# TestBoardV1.net
KiCad netlist of a schematic drawn in Altium Designer
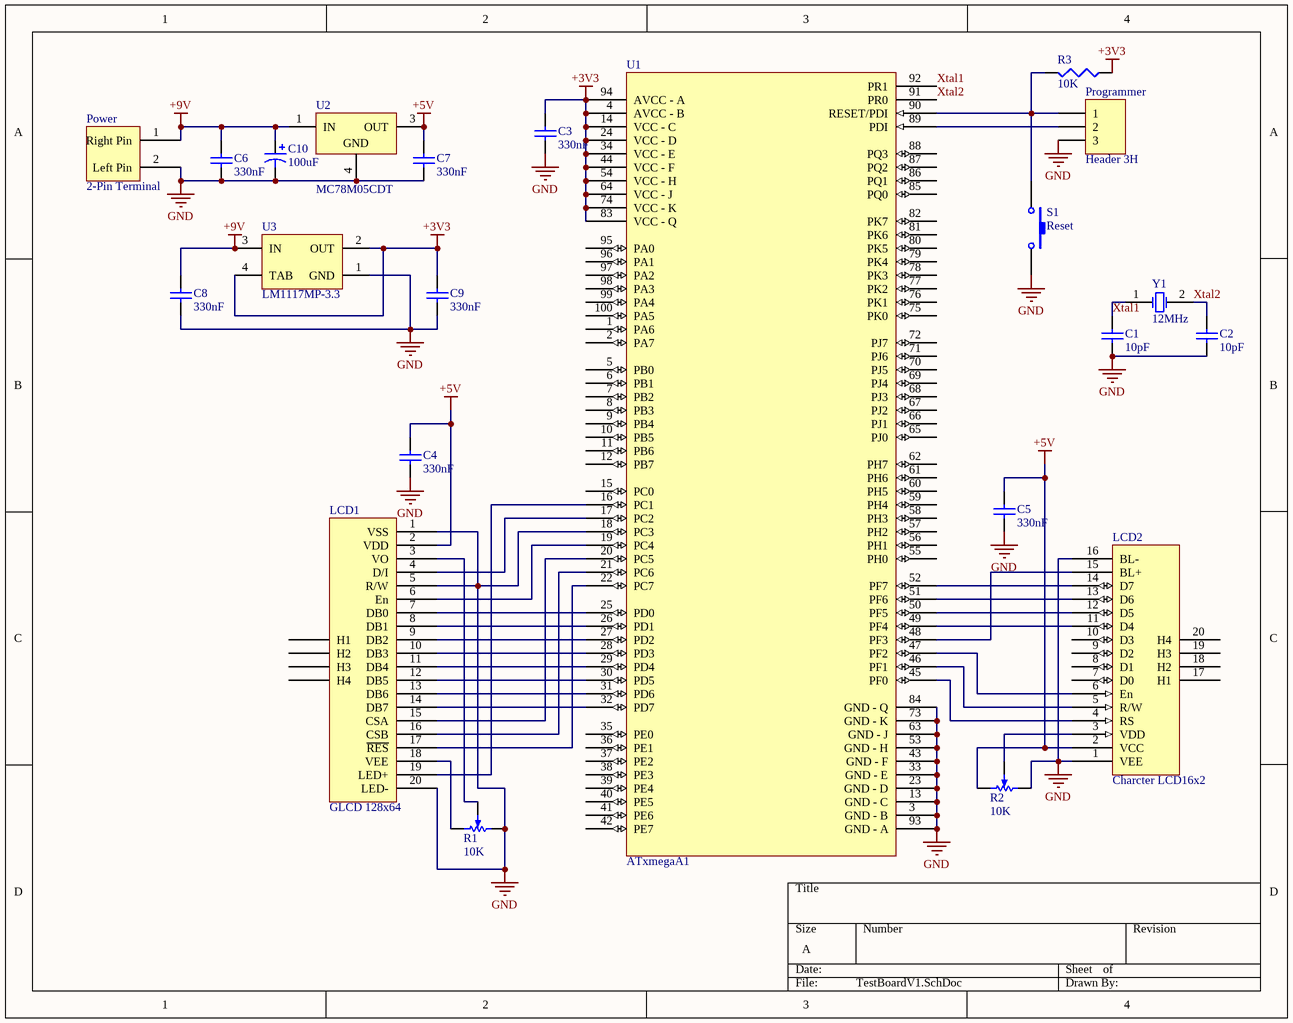
[diagram p0: TestBoardV1.SchDoc]

(export (version "E")
  (design (tool "Eeschema 10.0.6"))
  (components
    (comp (ref "C1")
      (value "10pF")
      (footprint "C1206")
      (description "Capacitor (Semiconductor SIM Model)")
      (fields (field (name "Comment") "Cap Semi") (field (name "PUBLISHER") "Altium Limited"))
      (libsource (lib "Miscellaneous Devices") (part "Cap Semi"))
    )
    (comp (ref "C2")
      (value "10pF")
      (footprint "C1206")
      (description "Capacitor (Semiconductor SIM Model)")
      (fields (field (name "Comment") "Cap Semi") (field (name "PUBLISHER") "Altium Limited"))
      (libsource (lib "Miscellaneous Devices") (part "Cap Semi"))
    )
    (comp (ref "C3")
      (value "330nF")
      (footprint "C1206")
      (description "Capacitor (Semiconductor SIM Model)")
      (fields (field (name "Comment") "Cap Semi") (field (name "PUBLISHER") "Altium Limited"))
      (libsource (lib "Miscellaneous Devices") (part "Cap Semi"))
    )
    (comp (ref "C4")
      (value "330nF")
      (footprint "C1206")
      (description "Capacitor (Semiconductor SIM Model)")
      (fields (field (name "Comment") "Cap Semi") (field (name "PUBLISHER") "Altium Limited"))
      (libsource (lib "Miscellaneous Devices") (part "Cap Semi"))
    )
    (comp (ref "C5")
      (value "330nF")
      (footprint "C1206")
      (description "Capacitor (Semiconductor SIM Model)")
      (fields (field (name "Comment") "Cap Semi") (field (name "PUBLISHER") "Altium Limited"))
      (libsource (lib "Miscellaneous Devices") (part "Cap Semi"))
    )
    (comp (ref "C6")
      (value "330nF")
      (footprint "C1206")
      (description "Capacitor (Semiconductor SIM Model)")
      (fields (field (name "Comment") "Cap Semi") (field (name "PUBLISHER") "Altium Limited"))
      (libsource (lib "Miscellaneous Devices") (part "Cap Semi"))
    )
    (comp (ref "C7")
      (value "330nF")
      (footprint "C1206")
      (description "Capacitor (Semiconductor SIM Model)")
      (fields (field (name "Comment") "Cap Semi") (field (name "PUBLISHER") "Altium Limited"))
      (libsource (lib "Miscellaneous Devices") (part "Cap Semi"))
    )
    (comp (ref "C8")
      (value "330nF")
      (footprint "C1206")
      (description "Capacitor (Semiconductor SIM Model)")
      (fields (field (name "Comment") "Cap Semi") (field (name "PUBLISHER") "Altium Limited"))
      (libsource (lib "Miscellaneous Devices") (part "Cap Semi"))
    )
    (comp (ref "C9")
      (value "330nF")
      (footprint "C1206")
      (description "Capacitor (Semiconductor SIM Model)")
      (fields (field (name "Comment") "Cap Semi") (field (name "PUBLISHER") "Altium Limited"))
      (libsource (lib "Miscellaneous Devices") (part "Cap Semi"))
    )
    (comp (ref "C10") (value "100uF") (footprint "Cap Pole-100u") (libsource (lib "MyLib") (part "Cap Pole")))
    (comp (ref "LCD1")
      (value "GLCD 128x64")
      (footprint "GLCD 128X64")
      (libsource (lib "MyLib") (part "GLCD 128x64"))
    )
    (comp (ref "LCD2")
      (value "Charcter LCD16x2")
      (footprint "LCD16x2")
      (libsource (lib "MyLib") (part "LCD16x2"))
    )
    (comp (ref "Power")
      (value "2-Pin Terminal")
      (footprint "2-pin Terminal")
      (libsource (lib "MyLib") (part "2-Pin Terminal"))
    )
    (comp (ref "Programmer")
      (value "Header 3H")
      (footprint "HDR1X3H")
      (description "Header, 3-Pin, Right Angle")
      (fields (field (name "PUBLISHER") "Altium Limited"))
      (libsource (lib "Miscellaneous Connectors") (part "Header 3H"))
    )
    (comp (ref "R1")
      (value "10K")
      (footprint "POT4MM-2")
      (description "Square Trimming Potentiometer")
      (fields (field (name "PUBLISHER") "Altium Limited"))
      (libsource (lib "Miscellaneous Devices") (part "RPot SM"))
    )
    (comp (ref "R2")
      (value "10K")
      (footprint "POT4MM-2")
      (description "Square Trimming Potentiometer")
      (fields (field (name "PUBLISHER") "Altium Limited"))
      (libsource (lib "Miscellaneous Devices") (part "RPot SM"))
    )
    (comp (ref "R3")
      (value "10K")
      (footprint "MELF-R3216-1206")
      (description "Resistor")
      (fields (field (name "Comment") "Res3") (field (name "PUBLISHER") "Altium Limited"))
      (libsource (lib "Miscellaneous Devices") (part "Res3"))
    )
    (comp (ref "S1")
      (value "Reset")
      (footprint "SMD_Switch")
      (description "Switch")
      (fields (field (name "PUBLISHER") "Altium Limited"))
      (libsource (lib "Miscellaneous Devices") (part "SW-PB"))
    )
    (comp (ref "U1")
      (value "ATxmegaA1")
      (footprint "TQFP100")
      (description "High Performance 8/16bit MCU")
      (libsource (lib "MyLib") (part "ATxMega_A1"))
    )
    (comp (ref "U2")
      (value "MC78M05CDT")
      (footprint "369A-03")
      (description "3-Terminal Medium-Current Positive Fixed Voltage Regulator")
      (fields (field (name "PUBLISHER") "Altium Limited"))
      (libsource (lib "Motorola Power Mgt Voltage Regulator") (part "MC78M05CDT"))
    )
    (comp (ref "U3")
      (value "LM1117MP-3.3")
      (footprint "MP04A_N")
      (description "800mA Low-Dropout Linear Regulator")
      (fields
        (field (name "MANUFACTURER") "National Semiconductor")
        (field (name "DIGIKEYPARTNUMBER") "LM1117MP-3.3CT-ND")
        (field (name "PUBLISHER") "Altium Limited")
      )
      (libsource (lib "NSC LDO") (part "LM1117MP-3.3"))
    )
    (comp (ref "Y1")
      (value "12MHz")
      (footprint "HC-49U")
      (description "Crystal Oscillator")
      (fields (field (name "PUBLISHER") "Altium Limited"))
      (libsource (lib "ECS Crystal Oscillator") (part "ECS-10-13-1"))
    )
  )
  (nets
    (net (code "1") (name "+3V3") (class "Default")
      (node (ref "C3") (pin "2") (pinfunction "2_2") (pintype "passive"))
      (node (ref "C9") (pin "2") (pinfunction "2_2") (pintype "passive"))
      (node (ref "R3") (pin "1") (pinfunction "1_1") (pintype "passive"))
      (node (ref "U1") (pin "14") (pinfunction "VCC_-_C_14") (pintype "power_in"))
      (node (ref "U1") (pin "24") (pinfunction "VCC_-_D_24") (pintype "power_in"))
      (node (ref "U1") (pin "34") (pinfunction "VCC_-_E_34") (pintype "power_in"))
      (node (ref "U1") (pin "4") (pinfunction "AVCC_-_B_4") (pintype "power_in"))
      (node (ref "U1") (pin "44") (pinfunction "VCC_-_F_44") (pintype "power_in"))
      (node (ref "U1") (pin "54") (pinfunction "VCC_-_H_54") (pintype "power_in"))
      (node (ref "U1") (pin "64") (pinfunction "VCC_-_J_64") (pintype "power_in"))
      (node (ref "U1") (pin "74") (pinfunction "VCC_-_K_74") (pintype "power_in"))
      (node (ref "U1") (pin "83") (pinfunction "VCC_-_Q_83") (pintype "power_in"))
      (node (ref "U1") (pin "94") (pinfunction "AVCC_-_A_94") (pintype "power_in"))
      (node (ref "U3") (pin "2") (pinfunction "OUT_2") (pintype "power_in"))
      (node (ref "U3") (pin "4") (pinfunction "TAB_4") (pintype "power_in"))
    )
    (net (code "2") (name "+5V") (class "Default")
      (node (ref "C4") (pin "2") (pinfunction "2_2") (pintype "passive"))
      (node (ref "C5") (pin "2") (pinfunction "2_2") (pintype "passive"))
      (node (ref "C7") (pin "2") (pinfunction "2_2") (pintype "passive"))
      (node (ref "LCD1") (pin "2") (pinfunction "VDD_2") (pintype "passive"))
      (node (ref "LCD2") (pin "2") (pinfunction "VCC_2") (pintype "power_in"))
      (node (ref "R2") (pin "CW") (pinfunction "+_CW") (pintype "passive"))
      (node (ref "U2") (pin "3") (pinfunction "OUT_3") (pintype "power_in"))
    )
    (net (code "3") (name "+9V") (class "Default")
      (node (ref "C10") (pin "1") (pinfunction "1_1") (pintype "passive"))
      (node (ref "C6") (pin "2") (pinfunction "2_2") (pintype "passive"))
      (node (ref "C8") (pin "2") (pinfunction "2_2") (pintype "passive"))
      (node (ref "Power") (pin "1") (pinfunction "Right_Pin_1") (pintype "power_in"))
      (node (ref "U2") (pin "1") (pinfunction "IN_1") (pintype "power_in"))
      (node (ref "U3") (pin "3") (pinfunction "IN_3") (pintype "power_in"))
    )
    (net (code "4") (name "/Xtal1") (class "Default")
      (node (ref "C1") (pin "1") (pinfunction "1_1") (pintype "passive"))
      (node (ref "U1") (pin "92") (pinfunction "PR1_92") (pintype "power_in"))
      (node (ref "Y1") (pin "1") (pinfunction "OSC1_1") (pintype "passive"))
    )
    (net (code "5") (name "/Xtal2") (class "Default")
      (node (ref "C2") (pin "2") (pinfunction "2_2") (pintype "passive"))
      (node (ref "U1") (pin "91") (pinfunction "PR0_91") (pintype "power_in"))
      (node (ref "Y1") (pin "2") (pinfunction "OSC2_2") (pintype "passive"))
    )
    (net (code "6") (name "GND") (class "Default")
      (node (ref "C1") (pin "2") (pinfunction "2_2") (pintype "passive"))
      (node (ref "C10") (pin "2") (pinfunction "2_2") (pintype "passive"))
      (node (ref "C2") (pin "1") (pinfunction "1_1") (pintype "passive"))
      (node (ref "C3") (pin "1") (pinfunction "1_1") (pintype "passive"))
      (node (ref "C4") (pin "1") (pinfunction "1_1") (pintype "passive"))
      (node (ref "C5") (pin "1") (pinfunction "1_1") (pintype "passive"))
      (node (ref "C6") (pin "1") (pinfunction "1_1") (pintype "passive"))
      (node (ref "C7") (pin "1") (pinfunction "1_1") (pintype "passive"))
      (node (ref "C8") (pin "1") (pinfunction "1_1") (pintype "passive"))
      (node (ref "C9") (pin "1") (pinfunction "1_1") (pintype "passive"))
      (node (ref "LCD1") (pin "1") (pinfunction "VSS_1") (pintype "passive"))
      (node (ref "LCD1") (pin "20") (pinfunction "LED-_20") (pintype "passive"))
      (node (ref "LCD1") (pin "5") (pinfunction "R/W_5") (pintype "passive"))
      (node (ref "LCD2") (pin "1") (pinfunction "VEE_1") (pintype "power_in"))
      (node (ref "LCD2") (pin "16") (pinfunction "BL-_16") (pintype "passive"))
      (node (ref "Power") (pin "2") (pinfunction "Left_Pin_2") (pintype "power_in"))
      (node (ref "Programmer") (pin "3") (pinfunction "3_3") (pintype "passive"))
      (node (ref "R1") (pin "CCW") (pinfunction "-_CCW") (pintype "passive"))
      (node (ref "R2") (pin "CCW") (pinfunction "-_CCW") (pintype "passive"))
      (node (ref "S1") (pin "1") (pinfunction "1_1") (pintype "passive"))
      (node (ref "U1") (pin "13") (pinfunction "GND_-_C_13") (pintype "power_in"))
      (node (ref "U1") (pin "18") (pinfunction "PC3_18") (pintype "bidirectional"))
      (node (ref "U1") (pin "23") (pinfunction "GND_-_D_23") (pintype "power_in"))
      (node (ref "U1") (pin "3") (pinfunction "GND_-_B_3") (pintype "power_in"))
      (node (ref "U1") (pin "33") (pinfunction "GND_-_E_33") (pintype "power_in"))
      (node (ref "U1") (pin "43") (pinfunction "GND_-_F_43") (pintype "power_in"))
      (node (ref "U1") (pin "53") (pinfunction "GND_-_H_53") (pintype "power_in"))
      (node (ref "U1") (pin "63") (pinfunction "GND_-_J_63") (pintype "power_in"))
      (node (ref "U1") (pin "73") (pinfunction "GND_-_K_73") (pintype "power_in"))
      (node (ref "U1") (pin "84") (pinfunction "GND_-_Q_84") (pintype "power_in"))
      (node (ref "U1") (pin "93") (pinfunction "GND_-_A_93") (pintype "power_in"))
      (node (ref "U2") (pin "4") (pinfunction "GND_4") (pintype "power_in"))
      (node (ref "U3") (pin "1") (pinfunction "GND_1") (pintype "power_in"))
    )
    (net (code "7") (name "Net-(LCD1-CSA)") (class "Default")
      (node (ref "LCD1") (pin "15") (pinfunction "CSA_15") (pintype "passive"))
      (node (ref "U1") (pin "20") (pinfunction "PC5_20") (pintype "bidirectional"))
    )
    (net (code "8") (name "Net-(LCD1-CSB)") (class "Default")
      (node (ref "LCD1") (pin "16") (pinfunction "CSB_16") (pintype "passive"))
      (node (ref "U1") (pin "21") (pinfunction "PC6_21") (pintype "bidirectional"))
    )
    (net (code "9") (name "Net-(LCD1-DB0)") (class "Default")
      (node (ref "LCD1") (pin "7") (pinfunction "DB0_7") (pintype "passive"))
      (node (ref "U1") (pin "25") (pinfunction "PD0_25") (pintype "bidirectional"))
    )
    (net (code "10") (name "Net-(LCD1-DB1)") (class "Default")
      (node (ref "LCD1") (pin "8") (pinfunction "DB1_8") (pintype "passive"))
      (node (ref "U1") (pin "26") (pinfunction "PD1_26") (pintype "bidirectional"))
    )
    (net (code "11") (name "Net-(LCD1-DB2)") (class "Default")
      (node (ref "LCD1") (pin "9") (pinfunction "DB2_9") (pintype "passive"))
      (node (ref "U1") (pin "27") (pinfunction "PD2_27") (pintype "bidirectional"))
    )
    (net (code "12") (name "Net-(LCD1-DB3)") (class "Default")
      (node (ref "LCD1") (pin "10") (pinfunction "DB3_10") (pintype "passive"))
      (node (ref "U1") (pin "28") (pinfunction "PD3_28") (pintype "bidirectional"))
    )
    (net (code "13") (name "Net-(LCD1-DB4)") (class "Default")
      (node (ref "LCD1") (pin "11") (pinfunction "DB4_11") (pintype "passive"))
      (node (ref "U1") (pin "29") (pinfunction "PD4_29") (pintype "bidirectional"))
    )
    (net (code "14") (name "Net-(LCD1-DB5)") (class "Default")
      (node (ref "LCD1") (pin "12") (pinfunction "DB5_12") (pintype "passive"))
      (node (ref "U1") (pin "30") (pinfunction "PD5_30") (pintype "bidirectional"))
    )
    (net (code "15") (name "Net-(LCD1-DB6)") (class "Default")
      (node (ref "LCD1") (pin "13") (pinfunction "DB6_13") (pintype "passive"))
      (node (ref "U1") (pin "31") (pinfunction "PD6_31") (pintype "bidirectional"))
    )
    (net (code "16") (name "Net-(LCD1-DB7)") (class "Default")
      (node (ref "LCD1") (pin "14") (pinfunction "DB7_14") (pintype "passive"))
      (node (ref "U1") (pin "32") (pinfunction "PD7_32") (pintype "bidirectional"))
    )
    (net (code "17") (name "Net-(LCD1-D{slash}I)") (class "Default")
      (node (ref "LCD1") (pin "4") (pinfunction "D/I_4") (pintype "passive"))
      (node (ref "U1") (pin "17") (pinfunction "PC2_17") (pintype "bidirectional"))
    )
    (net (code "18") (name "Net-(LCD1-En)") (class "Default")
      (node (ref "LCD1") (pin "6") (pinfunction "En_6") (pintype "passive"))
      (node (ref "U1") (pin "19") (pinfunction "PC4_19") (pintype "bidirectional"))
    )
    (net (code "19") (name "Net-(LCD1-LED+)") (class "Default")
      (node (ref "LCD1") (pin "19") (pinfunction "LED+_19") (pintype "passive"))
      (node (ref "U1") (pin "16") (pinfunction "PC1_16") (pintype "bidirectional"))
    )
    (net (code "20") (name "Net-(LCD1-VEE)") (class "Default")
      (node (ref "LCD1") (pin "18") (pinfunction "VEE_18") (pintype "passive"))
      (node (ref "R1") (pin "CW") (pinfunction "+_CW") (pintype "passive"))
    )
    (net (code "21") (name "Net-(LCD1-VO)") (class "Default")
      (node (ref "LCD1") (pin "3") (pinfunction "VO_3") (pintype "passive"))
      (node (ref "R1") (pin "W") (pinfunction "W_W") (pintype "passive"))
    )
    (net (code "22") (name "Net-(LCD1-~{RES})") (class "Default")
      (node (ref "LCD1") (pin "17") (pinfunction "~{RES}_17") (pintype "passive"))
      (node (ref "U1") (pin "22") (pinfunction "PC7_22") (pintype "bidirectional"))
    )
    (net (code "23") (name "Net-(LCD2-BL+)") (class "Default")
      (node (ref "LCD2") (pin "15") (pinfunction "BL+_15") (pintype "passive"))
      (node (ref "U1") (pin "48") (pinfunction "PF3_48") (pintype "bidirectional"))
    )
    (net (code "24") (name "Net-(LCD2-D4)") (class "Default")
      (node (ref "LCD2") (pin "11") (pinfunction "D4_11") (pintype "bidirectional"))
      (node (ref "U1") (pin "49") (pinfunction "PF4_49") (pintype "bidirectional"))
    )
    (net (code "25") (name "Net-(LCD2-D5)") (class "Default")
      (node (ref "LCD2") (pin "12") (pinfunction "D5_12") (pintype "bidirectional"))
      (node (ref "U1") (pin "50") (pinfunction "PF5_50") (pintype "bidirectional"))
    )
    (net (code "26") (name "Net-(LCD2-D6)") (class "Default")
      (node (ref "LCD2") (pin "13") (pinfunction "D6_13") (pintype "bidirectional"))
      (node (ref "U1") (pin "51") (pinfunction "PF6_51") (pintype "bidirectional"))
    )
    (net (code "27") (name "Net-(LCD2-D7)") (class "Default")
      (node (ref "LCD2") (pin "14") (pinfunction "D7_14") (pintype "bidirectional"))
      (node (ref "U1") (pin "52") (pinfunction "PF7_52") (pintype "bidirectional"))
    )
    (net (code "28") (name "Net-(LCD2-En)") (class "Default")
      (node (ref "LCD2") (pin "6") (pinfunction "En_6") (pintype "input"))
      (node (ref "U1") (pin "47") (pinfunction "PF2_47") (pintype "bidirectional"))
    )
    (net (code "29") (name "Net-(LCD2-RS)") (class "Default")
      (node (ref "LCD2") (pin "4") (pinfunction "RS_4") (pintype "input"))
      (node (ref "U1") (pin "45") (pinfunction "PF0_45") (pintype "bidirectional"))
    )
    (net (code "30") (name "Net-(LCD2-R{slash}W)") (class "Default")
      (node (ref "LCD2") (pin "5") (pinfunction "R/W_5") (pintype "input"))
      (node (ref "U1") (pin "46") (pinfunction "PF1_46") (pintype "bidirectional"))
    )
    (net (code "31") (name "Net-(LCD2-VDD)") (class "Default")
      (node (ref "LCD2") (pin "3") (pinfunction "VDD_3") (pintype "input"))
      (node (ref "R2") (pin "W") (pinfunction "W_W") (pintype "passive"))
    )
    (net (code "32") (name "Net-(U1-PDI)") (class "Default")
      (node (ref "Programmer") (pin "2") (pinfunction "2_2") (pintype "passive"))
      (node (ref "U1") (pin "89") (pinfunction "PDI_89") (pintype "input"))
    )
    (net (code "33") (name "Net-(U1-RESET{slash}PDI)") (class "Default")
      (node (ref "Programmer") (pin "1") (pinfunction "1_1") (pintype "passive"))
      (node (ref "R3") (pin "2") (pinfunction "2_2") (pintype "passive"))
      (node (ref "S1") (pin "2") (pinfunction "2_2") (pintype "passive"))
      (node (ref "U1") (pin "90") (pinfunction "RESET/PDI_90") (pintype "input"))
    )
    (net (code "34") (name "unconnected-(LCD1-H1-Pad21)") (class "Default")
      (node (ref "LCD1") (pin "21") (pinfunction "H1_21") (pintype "passive"))
    )
    (net (code "35") (name "unconnected-(LCD1-H2-Pad22)") (class "Default")
      (node (ref "LCD1") (pin "22") (pinfunction "H2_22") (pintype "passive"))
    )
    (net (code "36") (name "unconnected-(LCD1-H3-Pad23)") (class "Default")
      (node (ref "LCD1") (pin "23") (pinfunction "H3_23") (pintype "passive"))
    )
    (net (code "37") (name "unconnected-(LCD1-H4-Pad24)") (class "Default")
      (node (ref "LCD1") (pin "24") (pinfunction "H4_24") (pintype "passive"))
    )
    (net (code "38") (name "unconnected-(LCD2-D0-Pad7)") (class "Default")
      (node (ref "LCD2") (pin "7") (pinfunction "D0_7") (pintype "bidirectional"))
    )
    (net (code "39") (name "unconnected-(LCD2-D1-Pad8)") (class "Default")
      (node (ref "LCD2") (pin "8") (pinfunction "D1_8") (pintype "bidirectional"))
    )
    (net (code "40") (name "unconnected-(LCD2-D2-Pad9)") (class "Default")
      (node (ref "LCD2") (pin "9") (pinfunction "D2_9") (pintype "bidirectional"))
    )
    (net (code "41") (name "unconnected-(LCD2-D3-Pad10)") (class "Default")
      (node (ref "LCD2") (pin "10") (pinfunction "D3_10") (pintype "bidirectional"))
    )
    (net (code "42") (name "unconnected-(LCD2-H1-Pad17)") (class "Default")
      (node (ref "LCD2") (pin "17") (pinfunction "H1_17") (pintype "passive"))
    )
    (net (code "43") (name "unconnected-(LCD2-H2-Pad18)") (class "Default")
      (node (ref "LCD2") (pin "18") (pinfunction "H2_18") (pintype "passive"))
    )
    (net (code "44") (name "unconnected-(LCD2-H3-Pad19)") (class "Default")
      (node (ref "LCD2") (pin "19") (pinfunction "H3_19") (pintype "passive"))
    )
    (net (code "45") (name "unconnected-(LCD2-H4-Pad20)") (class "Default")
      (node (ref "LCD2") (pin "20") (pinfunction "H4_20") (pintype "passive"))
    )
    (net (code "46") (name "unconnected-(U1-PA0-Pad95)") (class "Default")
      (node (ref "U1") (pin "95") (pinfunction "PA0_95") (pintype "bidirectional"))
    )
    (net (code "47") (name "unconnected-(U1-PA1-Pad96)") (class "Default")
      (node (ref "U1") (pin "96") (pinfunction "PA1_96") (pintype "bidirectional"))
    )
    (net (code "48") (name "unconnected-(U1-PA2-Pad97)") (class "Default")
      (node (ref "U1") (pin "97") (pinfunction "PA2_97") (pintype "bidirectional"))
    )
    (net (code "49") (name "unconnected-(U1-PA3-Pad98)") (class "Default")
      (node (ref "U1") (pin "98") (pinfunction "PA3_98") (pintype "bidirectional"))
    )
    (net (code "50") (name "unconnected-(U1-PA4-Pad99)") (class "Default")
      (node (ref "U1") (pin "99") (pinfunction "PA4_99") (pintype "bidirectional"))
    )
    (net (code "51") (name "unconnected-(U1-PA5-Pad100)") (class "Default")
      (node (ref "U1") (pin "100") (pinfunction "PA5_100") (pintype "bidirectional"))
    )
    (net (code "52") (name "unconnected-(U1-PA6-Pad1)") (class "Default")
      (node (ref "U1") (pin "1") (pinfunction "PA6_1") (pintype "bidirectional"))
    )
    (net (code "53") (name "unconnected-(U1-PA7-Pad2)") (class "Default")
      (node (ref "U1") (pin "2") (pinfunction "PA7_2") (pintype "bidirectional"))
    )
    (net (code "54") (name "unconnected-(U1-PB0-Pad5)") (class "Default")
      (node (ref "U1") (pin "5") (pinfunction "PB0_5") (pintype "bidirectional"))
    )
    (net (code "55") (name "unconnected-(U1-PB1-Pad6)") (class "Default")
      (node (ref "U1") (pin "6") (pinfunction "PB1_6") (pintype "bidirectional"))
    )
    (net (code "56") (name "unconnected-(U1-PB2-Pad7)") (class "Default")
      (node (ref "U1") (pin "7") (pinfunction "PB2_7") (pintype "bidirectional"))
    )
    (net (code "57") (name "unconnected-(U1-PB3-Pad8)") (class "Default")
      (node (ref "U1") (pin "8") (pinfunction "PB3_8") (pintype "bidirectional"))
    )
    (net (code "58") (name "unconnected-(U1-PB4-Pad9)") (class "Default")
      (node (ref "U1") (pin "9") (pinfunction "PB4_9") (pintype "bidirectional"))
    )
    (net (code "59") (name "unconnected-(U1-PB5-Pad10)") (class "Default")
      (node (ref "U1") (pin "10") (pinfunction "PB5_10") (pintype "bidirectional"))
    )
    (net (code "60") (name "unconnected-(U1-PB6-Pad11)") (class "Default")
      (node (ref "U1") (pin "11") (pinfunction "PB6_11") (pintype "bidirectional"))
    )
    (net (code "61") (name "unconnected-(U1-PB7-Pad12)") (class "Default")
      (node (ref "U1") (pin "12") (pinfunction "PB7_12") (pintype "bidirectional"))
    )
    (net (code "62") (name "unconnected-(U1-PC0-Pad15)") (class "Default")
      (node (ref "U1") (pin "15") (pinfunction "PC0_15") (pintype "bidirectional"))
    )
    (net (code "63") (name "unconnected-(U1-PE0-Pad35)") (class "Default")
      (node (ref "U1") (pin "35") (pinfunction "PE0_35") (pintype "bidirectional"))
    )
    (net (code "64") (name "unconnected-(U1-PE1-Pad36)") (class "Default")
      (node (ref "U1") (pin "36") (pinfunction "PE1_36") (pintype "bidirectional"))
    )
    (net (code "65") (name "unconnected-(U1-PE2-Pad37)") (class "Default")
      (node (ref "U1") (pin "37") (pinfunction "PE2_37") (pintype "bidirectional"))
    )
    (net (code "66") (name "unconnected-(U1-PE3-Pad38)") (class "Default")
      (node (ref "U1") (pin "38") (pinfunction "PE3_38") (pintype "bidirectional"))
    )
    (net (code "67") (name "unconnected-(U1-PE4-Pad39)") (class "Default")
      (node (ref "U1") (pin "39") (pinfunction "PE4_39") (pintype "bidirectional"))
    )
    (net (code "68") (name "unconnected-(U1-PE5-Pad40)") (class "Default")
      (node (ref "U1") (pin "40") (pinfunction "PE5_40") (pintype "bidirectional"))
    )
    (net (code "69") (name "unconnected-(U1-PE6-Pad41)") (class "Default")
      (node (ref "U1") (pin "41") (pinfunction "PE6_41") (pintype "bidirectional"))
    )
    (net (code "70") (name "unconnected-(U1-PE7-Pad42)") (class "Default")
      (node (ref "U1") (pin "42") (pinfunction "PE7_42") (pintype "bidirectional"))
    )
    (net (code "71") (name "unconnected-(U1-PH0-Pad55)") (class "Default")
      (node (ref "U1") (pin "55") (pinfunction "PH0_55") (pintype "bidirectional"))
    )
    (net (code "72") (name "unconnected-(U1-PH1-Pad56)") (class "Default")
      (node (ref "U1") (pin "56") (pinfunction "PH1_56") (pintype "bidirectional"))
    )
    (net (code "73") (name "unconnected-(U1-PH2-Pad57)") (class "Default")
      (node (ref "U1") (pin "57") (pinfunction "PH2_57") (pintype "bidirectional"))
    )
    (net (code "74") (name "unconnected-(U1-PH3-Pad58)") (class "Default")
      (node (ref "U1") (pin "58") (pinfunction "PH3_58") (pintype "bidirectional"))
    )
    (net (code "75") (name "unconnected-(U1-PH4-Pad59)") (class "Default")
      (node (ref "U1") (pin "59") (pinfunction "PH4_59") (pintype "bidirectional"))
    )
    (net (code "76") (name "unconnected-(U1-PH5-Pad60)") (class "Default")
      (node (ref "U1") (pin "60") (pinfunction "PH5_60") (pintype "bidirectional"))
    )
    (net (code "77") (name "unconnected-(U1-PH6-Pad61)") (class "Default")
      (node (ref "U1") (pin "61") (pinfunction "PH6_61") (pintype "bidirectional"))
    )
    (net (code "78") (name "unconnected-(U1-PH7-Pad62)") (class "Default")
      (node (ref "U1") (pin "62") (pinfunction "PH7_62") (pintype "bidirectional"))
    )
    (net (code "79") (name "unconnected-(U1-PJ0-Pad65)") (class "Default")
      (node (ref "U1") (pin "65") (pinfunction "PJ0_65") (pintype "bidirectional"))
    )
    (net (code "80") (name "unconnected-(U1-PJ1-Pad66)") (class "Default")
      (node (ref "U1") (pin "66") (pinfunction "PJ1_66") (pintype "bidirectional"))
    )
    (net (code "81") (name "unconnected-(U1-PJ2-Pad67)") (class "Default")
      (node (ref "U1") (pin "67") (pinfunction "PJ2_67") (pintype "bidirectional"))
    )
    (net (code "82") (name "unconnected-(U1-PJ3-Pad68)") (class "Default")
      (node (ref "U1") (pin "68") (pinfunction "PJ3_68") (pintype "bidirectional"))
    )
    (net (code "83") (name "unconnected-(U1-PJ4-Pad69)") (class "Default")
      (node (ref "U1") (pin "69") (pinfunction "PJ4_69") (pintype "bidirectional"))
    )
    (net (code "84") (name "unconnected-(U1-PJ5-Pad70)") (class "Default")
      (node (ref "U1") (pin "70") (pinfunction "PJ5_70") (pintype "bidirectional"))
    )
    (net (code "85") (name "unconnected-(U1-PJ6-Pad71)") (class "Default")
      (node (ref "U1") (pin "71") (pinfunction "PJ6_71") (pintype "bidirectional"))
    )
    (net (code "86") (name "unconnected-(U1-PJ7-Pad72)") (class "Default")
      (node (ref "U1") (pin "72") (pinfunction "PJ7_72") (pintype "bidirectional"))
    )
    (net (code "87") (name "unconnected-(U1-PK0-Pad75)") (class "Default")
      (node (ref "U1") (pin "75") (pinfunction "PK0_75") (pintype "bidirectional"))
    )
    (net (code "88") (name "unconnected-(U1-PK1-Pad76)") (class "Default")
      (node (ref "U1") (pin "76") (pinfunction "PK1_76") (pintype "bidirectional"))
    )
    (net (code "89") (name "unconnected-(U1-PK2-Pad77)") (class "Default")
      (node (ref "U1") (pin "77") (pinfunction "PK2_77") (pintype "bidirectional"))
    )
    (net (code "90") (name "unconnected-(U1-PK3-Pad78)") (class "Default")
      (node (ref "U1") (pin "78") (pinfunction "PK3_78") (pintype "bidirectional"))
    )
    (net (code "91") (name "unconnected-(U1-PK4-Pad79)") (class "Default")
      (node (ref "U1") (pin "79") (pinfunction "PK4_79") (pintype "bidirectional"))
    )
    (net (code "92") (name "unconnected-(U1-PK5-Pad80)") (class "Default")
      (node (ref "U1") (pin "80") (pinfunction "PK5_80") (pintype "bidirectional"))
    )
    (net (code "93") (name "unconnected-(U1-PK6-Pad81)") (class "Default")
      (node (ref "U1") (pin "81") (pinfunction "PK6_81") (pintype "bidirectional"))
    )
    (net (code "94") (name "unconnected-(U1-PK7-Pad82)") (class "Default")
      (node (ref "U1") (pin "82") (pinfunction "PK7_82") (pintype "bidirectional"))
    )
    (net (code "95") (name "unconnected-(U1-PQ0-Pad85)") (class "Default")
      (node (ref "U1") (pin "85") (pinfunction "PQ0_85") (pintype "bidirectional"))
    )
    (net (code "96") (name "unconnected-(U1-PQ1-Pad86)") (class "Default")
      (node (ref "U1") (pin "86") (pinfunction "PQ1_86") (pintype "bidirectional"))
    )
    (net (code "97") (name "unconnected-(U1-PQ2-Pad87)") (class "Default")
      (node (ref "U1") (pin "87") (pinfunction "PQ2_87") (pintype "bidirectional"))
    )
    (net (code "98") (name "unconnected-(U1-PQ3-Pad88)") (class "Default")
      (node (ref "U1") (pin "88") (pinfunction "PQ3_88") (pintype "bidirectional"))
    )
  )
)
